# Low_Side_Drivers.net
KiCad netlist of a schematic drawn in Altium Designer
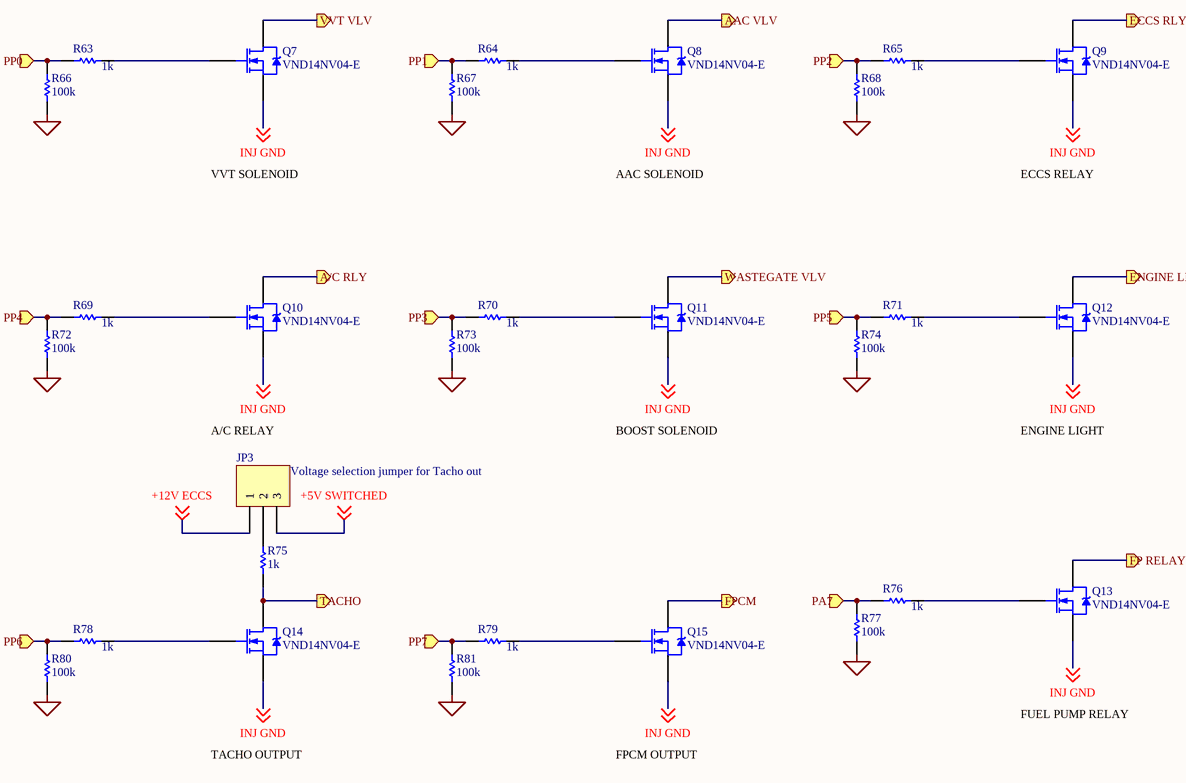
[diagram p0: Low Side Drivers.SchDoc]

(export (version "E")
  (design (tool "Eeschema 10.0.6"))
  (components
    (comp (ref "JP3")
      (value "Voltage selection jumper for Tacho out")
      (footprint "HDR1X3")
      (description "Header, 3-Pin")
      (fields (field (name "PUBLISHER") "Altium Limited"))
      (libsource (lib "Miscellaneous Connectors") (part "Header 3"))
    )
    (comp (ref "Q7")
      (value "VND14NV04-E")
      (footprint "TO-220AB")
      (description "HEXFET Power MOSFET")
      (fields (field (name "PUBLISHER") "Altium Limited"))
      (libsource (lib "IR Discrete MOSFET - Power") (part "IRL520N"))
    )
    (comp (ref "Q8")
      (value "VND14NV04-E")
      (footprint "TO-220AB")
      (description "HEXFET Power MOSFET")
      (fields (field (name "PUBLISHER") "Altium Limited"))
      (libsource (lib "IR Discrete MOSFET - Power") (part "IRL520N"))
    )
    (comp (ref "Q9")
      (value "VND14NV04-E")
      (footprint "TO-220AB")
      (description "HEXFET Power MOSFET")
      (fields (field (name "PUBLISHER") "Altium Limited"))
      (libsource (lib "IR Discrete MOSFET - Power") (part "IRL520N"))
    )
    (comp (ref "Q10")
      (value "VND14NV04-E")
      (footprint "TO-220AB")
      (description "HEXFET Power MOSFET")
      (fields (field (name "PUBLISHER") "Altium Limited"))
      (libsource (lib "IR Discrete MOSFET - Power") (part "IRL520N"))
    )
    (comp (ref "Q11")
      (value "VND14NV04-E")
      (footprint "TO-220AB")
      (description "HEXFET Power MOSFET")
      (fields (field (name "PUBLISHER") "Altium Limited"))
      (libsource (lib "IR Discrete MOSFET - Power") (part "IRL520N"))
    )
    (comp (ref "Q12")
      (value "VND14NV04-E")
      (footprint "TO-220AB")
      (description "HEXFET Power MOSFET")
      (fields (field (name "PUBLISHER") "Altium Limited"))
      (libsource (lib "IR Discrete MOSFET - Power") (part "IRL520N"))
    )
    (comp (ref "Q13")
      (value "VND14NV04-E")
      (footprint "TO-220AB")
      (description "HEXFET Power MOSFET")
      (fields (field (name "PUBLISHER") "Altium Limited"))
      (libsource (lib "IR Discrete MOSFET - Power") (part "IRL520N"))
    )
    (comp (ref "Q14")
      (value "VND14NV04-E")
      (footprint "TO-220AB")
      (description "HEXFET Power MOSFET")
      (fields (field (name "PUBLISHER") "Altium Limited"))
      (libsource (lib "IR Discrete MOSFET - Power") (part "IRL520N"))
    )
    (comp (ref "Q15")
      (value "VND14NV04-E")
      (footprint "TO-220AB")
      (description "HEXFET Power MOSFET")
      (fields (field (name "PUBLISHER") "Altium Limited"))
      (libsource (lib "IR Discrete MOSFET - Power") (part "IRL520N"))
    )
    (comp (ref "R63")
      (value "1k")
      (footprint "AXIAL-0.3")
      (description "Resistor")
      (fields (field (name "PUBLISHER") "Altium Limited"))
      (libsource (lib "Miscellaneous Devices") (part "Res1"))
    )
    (comp (ref "R64")
      (value "1k")
      (footprint "AXIAL-0.3")
      (description "Resistor")
      (fields (field (name "PUBLISHER") "Altium Limited"))
      (libsource (lib "Miscellaneous Devices") (part "Res1"))
    )
    (comp (ref "R65")
      (value "1k")
      (footprint "AXIAL-0.3")
      (description "Resistor")
      (fields (field (name "PUBLISHER") "Altium Limited"))
      (libsource (lib "Miscellaneous Devices") (part "Res1"))
    )
    (comp (ref "R66")
      (value "100k")
      (footprint "AXIAL-0.3")
      (description "Resistor")
      (fields (field (name "PUBLISHER") "Altium Limited"))
      (libsource (lib "Miscellaneous Devices") (part "Res1"))
    )
    (comp (ref "R67")
      (value "100k")
      (footprint "AXIAL-0.3")
      (description "Resistor")
      (fields (field (name "PUBLISHER") "Altium Limited"))
      (libsource (lib "Miscellaneous Devices") (part "Res1"))
    )
    (comp (ref "R68")
      (value "100k")
      (footprint "AXIAL-0.3")
      (description "Resistor")
      (fields (field (name "PUBLISHER") "Altium Limited"))
      (libsource (lib "Miscellaneous Devices") (part "Res1"))
    )
    (comp (ref "R69")
      (value "1k")
      (footprint "AXIAL-0.3")
      (description "Resistor")
      (fields (field (name "PUBLISHER") "Altium Limited"))
      (libsource (lib "Miscellaneous Devices") (part "Res1"))
    )
    (comp (ref "R70")
      (value "1k")
      (footprint "AXIAL-0.3")
      (description "Resistor")
      (fields (field (name "PUBLISHER") "Altium Limited"))
      (libsource (lib "Miscellaneous Devices") (part "Res1"))
    )
    (comp (ref "R71")
      (value "1k")
      (footprint "AXIAL-0.3")
      (description "Resistor")
      (fields (field (name "PUBLISHER") "Altium Limited"))
      (libsource (lib "Miscellaneous Devices") (part "Res1"))
    )
    (comp (ref "R72")
      (value "100k")
      (footprint "AXIAL-0.3")
      (description "Resistor")
      (fields (field (name "PUBLISHER") "Altium Limited"))
      (libsource (lib "Miscellaneous Devices") (part "Res1"))
    )
    (comp (ref "R73")
      (value "100k")
      (footprint "AXIAL-0.3")
      (description "Resistor")
      (fields (field (name "PUBLISHER") "Altium Limited"))
      (libsource (lib "Miscellaneous Devices") (part "Res1"))
    )
    (comp (ref "R74")
      (value "100k")
      (footprint "AXIAL-0.3")
      (description "Resistor")
      (fields (field (name "PUBLISHER") "Altium Limited"))
      (libsource (lib "Miscellaneous Devices") (part "Res1"))
    )
    (comp (ref "R75")
      (value "1k")
      (footprint "AXIAL-0.3")
      (description "Resistor")
      (fields (field (name "PUBLISHER") "Altium Limited"))
      (libsource (lib "Miscellaneous Devices") (part "Res1"))
    )
    (comp (ref "R76")
      (value "1k")
      (footprint "AXIAL-0.3")
      (description "Resistor")
      (fields (field (name "PUBLISHER") "Altium Limited"))
      (libsource (lib "Miscellaneous Devices") (part "Res1"))
    )
    (comp (ref "R77")
      (value "100k")
      (footprint "AXIAL-0.3")
      (description "Resistor")
      (fields (field (name "PUBLISHER") "Altium Limited"))
      (libsource (lib "Miscellaneous Devices") (part "Res1"))
    )
    (comp (ref "R78")
      (value "1k")
      (footprint "AXIAL-0.3")
      (description "Resistor")
      (fields (field (name "PUBLISHER") "Altium Limited"))
      (libsource (lib "Miscellaneous Devices") (part "Res1"))
    )
    (comp (ref "R79")
      (value "1k")
      (footprint "AXIAL-0.3")
      (description "Resistor")
      (fields (field (name "PUBLISHER") "Altium Limited"))
      (libsource (lib "Miscellaneous Devices") (part "Res1"))
    )
    (comp (ref "R80")
      (value "100k")
      (footprint "AXIAL-0.3")
      (description "Resistor")
      (fields (field (name "PUBLISHER") "Altium Limited"))
      (libsource (lib "Miscellaneous Devices") (part "Res1"))
    )
    (comp (ref "R81")
      (value "100k")
      (footprint "AXIAL-0.3")
      (description "Resistor")
      (fields (field (name "PUBLISHER") "Altium Limited"))
      (libsource (lib "Miscellaneous Devices") (part "Res1"))
    )
  )
  (nets
    (net (code "1") (name "+5V SWITCHED") (class "Default")
      (node (ref "JP3") (pin "3") (pinfunction "3_3") (pintype "passive"))
    )
    (net (code "2") (name "+12V ECCS") (class "Default")
      (node (ref "JP3") (pin "1") (pinfunction "1_1") (pintype "passive"))
    )
    (net (code "3") (name "/AAC VLV") (class "Default")
      (node (ref "Q8") (pin "2") (pinfunction "D_2") (pintype "passive"))
    )
    (net (code "4") (name "/A{slash}C RLY") (class "Default")
      (node (ref "Q10") (pin "2") (pinfunction "D_2") (pintype "passive"))
    )
    (net (code "5") (name "/ECCS RLY") (class "Default")
      (node (ref "Q9") (pin "2") (pinfunction "D_2") (pintype "passive"))
    )
    (net (code "6") (name "/ENGINE LIGHT") (class "Default")
      (node (ref "Q12") (pin "2") (pinfunction "D_2") (pintype "passive"))
    )
    (net (code "7") (name "/FP RELAY") (class "Default")
      (node (ref "Q13") (pin "2") (pinfunction "D_2") (pintype "passive"))
    )
    (net (code "8") (name "/FPCM") (class "Default")
      (node (ref "Q15") (pin "2") (pinfunction "D_2") (pintype "passive"))
    )
    (net (code "9") (name "/PA7") (class "Default")
      (node (ref "R76") (pin "1") (pinfunction "1_1") (pintype "passive"))
      (node (ref "R77") (pin "2") (pinfunction "2_2") (pintype "passive"))
    )
    (net (code "10") (name "/PP0") (class "Default")
      (node (ref "R63") (pin "1") (pinfunction "1_1") (pintype "passive"))
      (node (ref "R66") (pin "2") (pinfunction "2_2") (pintype "passive"))
    )
    (net (code "11") (name "/PP1") (class "Default")
      (node (ref "R64") (pin "1") (pinfunction "1_1") (pintype "passive"))
      (node (ref "R67") (pin "2") (pinfunction "2_2") (pintype "passive"))
    )
    (net (code "12") (name "/PP2") (class "Default")
      (node (ref "R65") (pin "1") (pinfunction "1_1") (pintype "passive"))
      (node (ref "R68") (pin "2") (pinfunction "2_2") (pintype "passive"))
    )
    (net (code "13") (name "/PP3") (class "Default")
      (node (ref "R70") (pin "1") (pinfunction "1_1") (pintype "passive"))
      (node (ref "R73") (pin "2") (pinfunction "2_2") (pintype "passive"))
    )
    (net (code "14") (name "/PP4") (class "Default")
      (node (ref "R69") (pin "1") (pinfunction "1_1") (pintype "passive"))
      (node (ref "R72") (pin "2") (pinfunction "2_2") (pintype "passive"))
    )
    (net (code "15") (name "/PP5") (class "Default")
      (node (ref "R71") (pin "1") (pinfunction "1_1") (pintype "passive"))
      (node (ref "R74") (pin "2") (pinfunction "2_2") (pintype "passive"))
    )
    (net (code "16") (name "/PP6") (class "Default")
      (node (ref "R78") (pin "1") (pinfunction "1_1") (pintype "passive"))
      (node (ref "R80") (pin "2") (pinfunction "2_2") (pintype "passive"))
    )
    (net (code "17") (name "/PP7") (class "Default")
      (node (ref "R79") (pin "1") (pinfunction "1_1") (pintype "passive"))
      (node (ref "R81") (pin "2") (pinfunction "2_2") (pintype "passive"))
    )
    (net (code "18") (name "/TACHO") (class "Default")
      (node (ref "Q14") (pin "2") (pinfunction "D_2") (pintype "passive"))
      (node (ref "R75") (pin "1") (pinfunction "1_1") (pintype "passive"))
    )
    (net (code "19") (name "/VVT VLV") (class "Default")
      (node (ref "Q7") (pin "2") (pinfunction "D_2") (pintype "passive"))
    )
    (net (code "20") (name "/WASTEGATE VLV") (class "Default")
      (node (ref "Q11") (pin "2") (pinfunction "D_2") (pintype "passive"))
    )
    (net (code "21") (name "<NO NET>") (class "Default")
      (node (ref "R66") (pin "1") (pinfunction "1_1") (pintype "passive"))
      (node (ref "R67") (pin "1") (pinfunction "1_1") (pintype "passive"))
      (node (ref "R68") (pin "1") (pinfunction "1_1") (pintype "passive"))
      (node (ref "R72") (pin "1") (pinfunction "1_1") (pintype "passive"))
      (node (ref "R73") (pin "1") (pinfunction "1_1") (pintype "passive"))
      (node (ref "R74") (pin "1") (pinfunction "1_1") (pintype "passive"))
      (node (ref "R77") (pin "1") (pinfunction "1_1") (pintype "passive"))
      (node (ref "R80") (pin "1") (pinfunction "1_1") (pintype "passive"))
      (node (ref "R81") (pin "1") (pinfunction "1_1") (pintype "passive"))
    )
    (net (code "22") (name "INJ GND") (class "Default")
      (node (ref "Q10") (pin "3") (pinfunction "S_3") (pintype "passive"))
      (node (ref "Q11") (pin "3") (pinfunction "S_3") (pintype "passive"))
      (node (ref "Q12") (pin "3") (pinfunction "S_3") (pintype "passive"))
      (node (ref "Q13") (pin "3") (pinfunction "S_3") (pintype "passive"))
      (node (ref "Q14") (pin "3") (pinfunction "S_3") (pintype "passive"))
      (node (ref "Q15") (pin "3") (pinfunction "S_3") (pintype "passive"))
      (node (ref "Q7") (pin "3") (pinfunction "S_3") (pintype "passive"))
      (node (ref "Q8") (pin "3") (pinfunction "S_3") (pintype "passive"))
      (node (ref "Q9") (pin "3") (pinfunction "S_3") (pintype "passive"))
    )
    (net (code "23") (name "Net-(JP3-Pad2)") (class "Default")
      (node (ref "JP3") (pin "2") (pinfunction "2_2") (pintype "passive"))
      (node (ref "R75") (pin "2") (pinfunction "2_2") (pintype "passive"))
    )
    (net (code "24") (name "Net-(Q7-G)") (class "Default")
      (node (ref "Q7") (pin "1") (pinfunction "G_1") (pintype "passive"))
      (node (ref "R63") (pin "2") (pinfunction "2_2") (pintype "passive"))
    )
    (net (code "25") (name "Net-(Q8-G)") (class "Default")
      (node (ref "Q8") (pin "1") (pinfunction "G_1") (pintype "passive"))
      (node (ref "R64") (pin "2") (pinfunction "2_2") (pintype "passive"))
    )
    (net (code "26") (name "Net-(Q9-G)") (class "Default")
      (node (ref "Q9") (pin "1") (pinfunction "G_1") (pintype "passive"))
      (node (ref "R65") (pin "2") (pinfunction "2_2") (pintype "passive"))
    )
    (net (code "27") (name "Net-(Q10-G)") (class "Default")
      (node (ref "Q10") (pin "1") (pinfunction "G_1") (pintype "passive"))
      (node (ref "R69") (pin "2") (pinfunction "2_2") (pintype "passive"))
    )
    (net (code "28") (name "Net-(Q11-G)") (class "Default")
      (node (ref "Q11") (pin "1") (pinfunction "G_1") (pintype "passive"))
      (node (ref "R70") (pin "2") (pinfunction "2_2") (pintype "passive"))
    )
    (net (code "29") (name "Net-(Q12-G)") (class "Default")
      (node (ref "Q12") (pin "1") (pinfunction "G_1") (pintype "passive"))
      (node (ref "R71") (pin "2") (pinfunction "2_2") (pintype "passive"))
    )
    (net (code "30") (name "Net-(Q13-G)") (class "Default")
      (node (ref "Q13") (pin "1") (pinfunction "G_1") (pintype "passive"))
      (node (ref "R76") (pin "2") (pinfunction "2_2") (pintype "passive"))
    )
    (net (code "31") (name "Net-(Q14-G)") (class "Default")
      (node (ref "Q14") (pin "1") (pinfunction "G_1") (pintype "passive"))
      (node (ref "R78") (pin "2") (pinfunction "2_2") (pintype "passive"))
    )
    (net (code "32") (name "Net-(Q15-G)") (class "Default")
      (node (ref "Q15") (pin "1") (pinfunction "G_1") (pintype "passive"))
      (node (ref "R79") (pin "2") (pinfunction "2_2") (pintype "passive"))
    )
  )
)
